# IcantFindFileName.net
KiCad netlist of a schematic drawn in Altium Designer
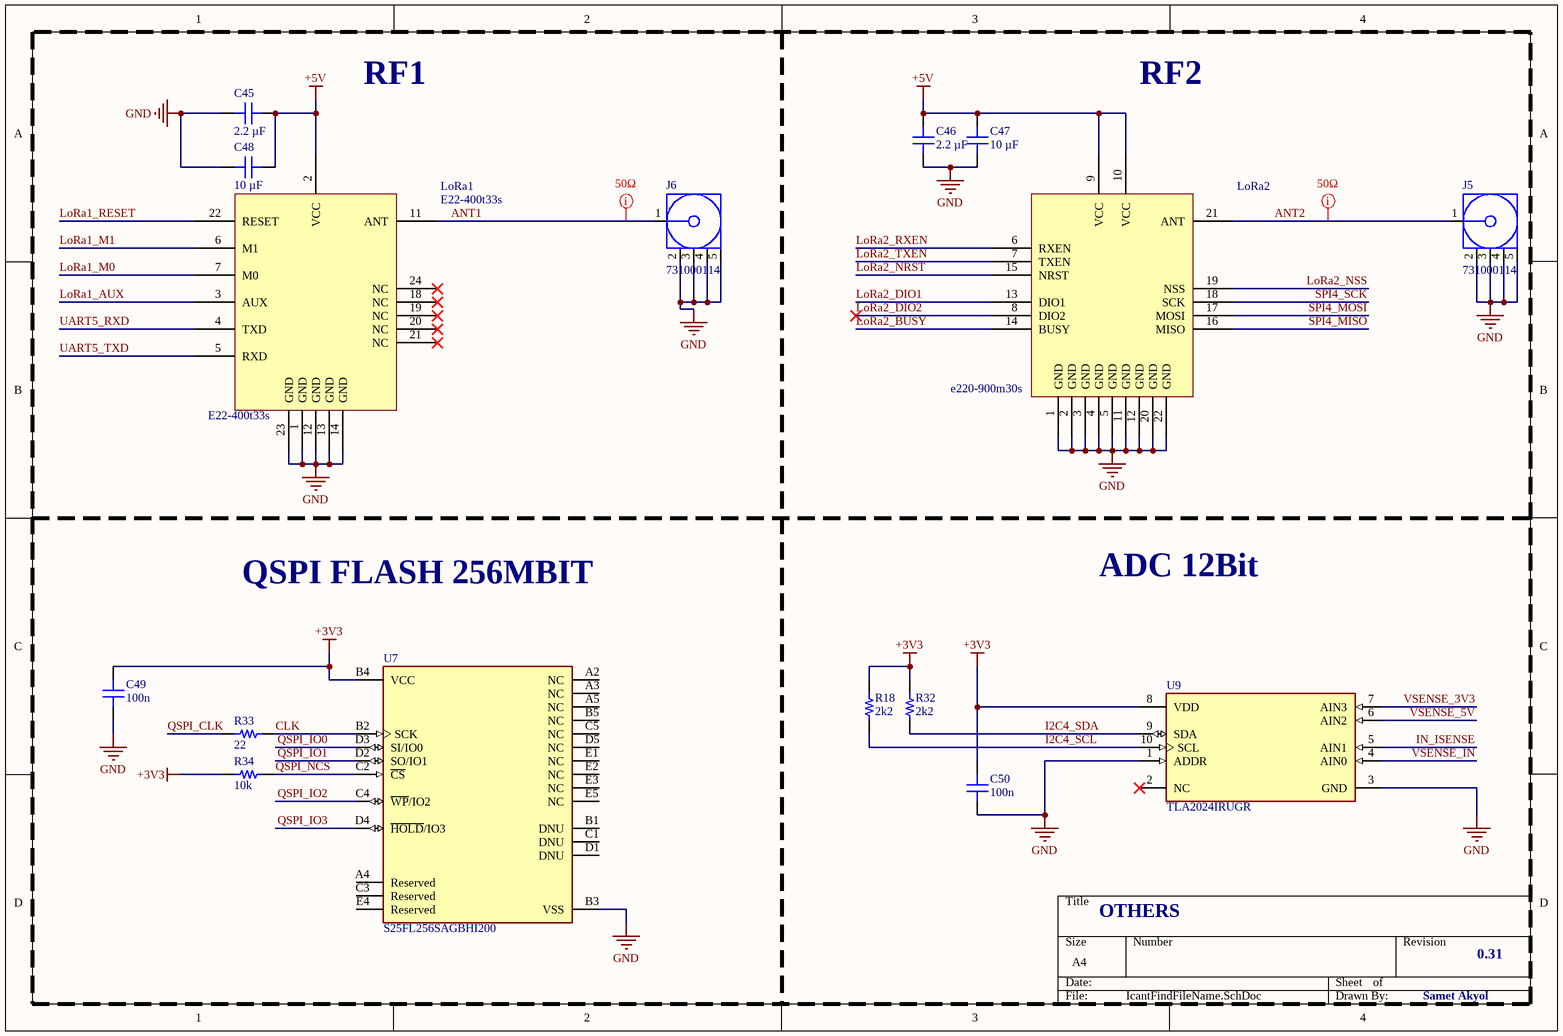
[diagram p0: IcantFindFileName.SchDoc]

(export (version "E")
  (design (tool "Eeschema 10.0.6"))
  (components
    (comp (ref "C45")
      (value "2.2 µF")
      (footprint "CAP 0805_2012")
      (description "CAP CER 2.2UF 25V X7R 0805")
      (fields (field (name "PART NUMBER") "TMK212B7225MG-TR") (field (name "MANUFACTURER") "Taiyo Yuden"))
      (libsource (lib "Celestial Altium Library - altium_library") (part "Capacitor"))
    )
    (comp (ref "C46")
      (value "2.2 µF")
      (footprint "CAP 0805_2012")
      (description "CAP CER 2.2UF 25V X7R 0805")
      (fields (field (name "PART NUMBER") "TMK212B7225MG-TR") (field (name "MANUFACTURER") "Taiyo Yuden"))
      (libsource (lib "Celestial Altium Library - altium_library") (part "Capacitor"))
    )
    (comp (ref "C47")
      (value "10 µF")
      (footprint "CAP 0805_2012")
      (description "CAP CER 10UF 16V X6S 0805")
      (fields
        (field (name "PART NUMBER") "C2012X6S1C106K125AC")
        (field (name "MANUFACTURER") "TDK Corporation")
      )
      (libsource (lib "Celestial Altium Library - altium_library") (part "Capacitor"))
    )
    (comp (ref "C48")
      (value "10 µF")
      (footprint "CAP 0805_2012")
      (description "CAP CER 10UF 16V X6S 0805")
      (fields
        (field (name "PART NUMBER") "C2012X6S1C106K125AC")
        (field (name "MANUFACTURER") "TDK Corporation")
      )
      (libsource (lib "Celestial Altium Library - altium_library") (part "Capacitor"))
    )
    (comp (ref "C49")
      (value "100n")
      (footprint "CAP 0402_1005")
      (description "CAP CER 100NF 10V X7R 0402")
      (fields
        (field (name "PART NUMBER") "CL05B104KP5VPNC")
        (field (name "MANUFACTURER") "Samsung Electro-Mechanics")
      )
      (libsource (lib "Celestial Altium Library - altium_library") (part "Capacitor"))
    )
    (comp (ref "C50")
      (value "100n")
      (footprint "CAP 0402_1005")
      (description "CAP CER 100NF 10V X7R 0402")
      (fields
        (field (name "PART NUMBER") "CL05B104KP5VPNC")
        (field (name "MANUFACTURER") "Samsung Electro-Mechanics")
      )
      (libsource (lib "Celestial Altium Library - altium_library") (part "Capacitor"))
    )
    (comp (ref "J5")
      (value "731000114")
      (footprint "MOLX-731000114_V")
      (description "SMA Right-Angle PCB Jack Receptacle, Brass Body, Gold Plated, 50 Ohm, 5-Pin THD, RoHS, Tray")
      (fields (field (name "MANUFACTURER") "Molex"))
      (libsource (lib "Altium Content Vault") (part "CN-S-4F-RF5"))
    )
    (comp (ref "J6")
      (value "731000114")
      (footprint "MOLX-731000114_V")
      (description "SMA Right-Angle PCB Jack Receptacle, Brass Body, Gold Plated, 50 Ohm, 5-Pin THD, RoHS, Tray")
      (fields (field (name "MANUFACTURER") "Molex"))
      (libsource (lib "Altium Content Vault") (part "CN-S-4F-RF5"))
    )
    (comp (ref "LoRa1")
      (value "E22-400t33s")
      (footprint "E32-433T33S")
      (libsource (lib "LoraE220-400t33s") (part "LoRa"))
    )
    (comp (ref "LoRa2")
      (value "e220-900m30s")
      (footprint "PE220-900M30S")
      (libsource (lib "LoRaE220-900m30s") (part "LoRaE220-900m30s"))
    )
    (comp (ref "R18")
      (value "2k2")
      (footprint "RES 0402_1005")
      (description "RES 10K OHM 0.1% 1/10W 0402")
      (fields
        (field (name "PART NUMBER") "RP73PF1E10KBTD")
        (field (name "MANUFACTURER") "TE Connectivity Passive Product")
      )
      (libsource (lib "Celestial Altium Library - altium_library") (part "Resistor"))
    )
    (comp (ref "R32")
      (value "2k2")
      (footprint "RES 0402_1005")
      (description "RES 10K OHM 0.1% 1/10W 0402")
      (fields
        (field (name "PART NUMBER") "RP73PF1E10KBTD")
        (field (name "MANUFACTURER") "TE Connectivity Passive Product")
      )
      (libsource (lib "Celestial Altium Library - altium_library") (part "Resistor"))
    )
    (comp (ref "R33")
      (value "22")
      (footprint "RES 0402_1005")
      (description "RES SMD 22 OHM 0.5% 1/16W 0402")
      (fields
        (field (name "PART NUMBER") "ERA-2AKD220X")
        (field (name "MANUFACTURER") "Panasonic Electronic Components")
      )
      (libsource (lib "Celestial Altium Library - altium_library") (part "Resistor"))
    )
    (comp (ref "R34")
      (value "10k")
      (footprint "RES 0402_1005")
      (description "RES 10K OHM 0.1% 1/10W 0402")
      (fields
        (field (name "PART NUMBER") "RP73PF1E10KBTD")
        (field (name "MANUFACTURER") "TE Connectivity Passive Product")
      )
      (libsource (lib "Celestial Altium Library - altium_library") (part "Resistor"))
    )
    (comp (ref "U7")
      (value "S25FL256SAGBHI200")
      (footprint "FP-002-15534-MFG")
      (description "IC FLASH 256M SPI 133MHZ 24BGA")
      (fields
        (field (name "MANUFACTURER") "Cypress Semiconductor")
        (field (name "OCTOPART") "https://octopart.com/s25fl256sagbhi200-cypress+semiconductor-65153244")
      )
      (libsource (lib "Altium Content Vault") (part "c77b842a4ee4074ef0a45385ad30001"))
    )
    (comp (ref "U9")
      (value "TLA2024IRUGR")
      (footprint "FP-RUG0010A-MFG")
      (description "IC ADC 12BIT SIGMA-DELTA 10X2QFN")
      (libsource (lib "Altium Content Vault") (part "eb3f1feaf096e0a4fed058628c4118d"))
    )
  )
  (nets
    (net (code "1") (name "+3V3") (class "Default")
      (node (ref "C49") (pin "2") (pinfunction "2_2") (pintype "passive"))
      (node (ref "C50") (pin "2") (pinfunction "2_2") (pintype "passive"))
      (node (ref "R18") (pin "2") (pinfunction "2_2") (pintype "passive"))
      (node (ref "R32") (pin "2") (pinfunction "2_2") (pintype "passive"))
      (node (ref "R34") (pin "2") (pinfunction "2_2") (pintype "passive"))
      (node (ref "U7") (pin "B4") (pinfunction "VCC_B4") (pintype "power_in"))
      (node (ref "U9") (pin "8") (pinfunction "VDD_8") (pintype "power_in"))
    )
    (net (code "2") (name "+5V") (class "Default")
      (node (ref "C45") (pin "2") (pinfunction "2_2") (pintype "passive"))
      (node (ref "C46") (pin "2") (pinfunction "2_2") (pintype "passive"))
      (node (ref "C47") (pin "2") (pinfunction "2_2") (pintype "passive"))
      (node (ref "C48") (pin "2") (pinfunction "2_2") (pintype "passive"))
      (node (ref "LoRa1") (pin "2") (pinfunction "VCC_2") (pintype "passive"))
      (node (ref "LoRa2") (pin "10") (pinfunction "VCC_10") (pintype "passive"))
      (node (ref "LoRa2") (pin "9") (pinfunction "VCC_9") (pintype "passive"))
    )
    (net (code "3") (name "/ANT1") (class "Default")
      (node (ref "J6") (pin "1") (pinfunction "1_1") (pintype "passive"))
      (node (ref "LoRa1") (pin "11") (pinfunction "ANT_11") (pintype "passive"))
    )
    (net (code "4") (name "/ANT2") (class "Default")
      (node (ref "J5") (pin "1") (pinfunction "1_1") (pintype "passive"))
      (node (ref "LoRa2") (pin "21") (pinfunction "ANT_21") (pintype "passive"))
    )
    (net (code "5") (name "/CLK") (class "Default")
      (node (ref "R33") (pin "2") (pinfunction "2_2") (pintype "passive"))
      (node (ref "U7") (pin "B2") (pinfunction "SCK_B2") (pintype "input"))
    )
    (net (code "6") (name "/I2C4_SCL") (class "Default")
      (node (ref "R18") (pin "1") (pinfunction "1_1") (pintype "passive"))
      (node (ref "U9") (pin "10") (pinfunction "SCL_10") (pintype "input"))
    )
    (net (code "7") (name "/I2C4_SDA") (class "Default")
      (node (ref "R32") (pin "1") (pinfunction "1_1") (pintype "passive"))
      (node (ref "U9") (pin "9") (pinfunction "SDA_9") (pintype "bidirectional"))
    )
    (net (code "8") (name "/IN_ISENSE") (class "Default")
      (node (ref "U9") (pin "5") (pinfunction "AIN1_5") (pintype "input"))
    )
    (net (code "9") (name "/LoRa1_AUX") (class "Default")
      (node (ref "LoRa1") (pin "3") (pinfunction "AUX_3") (pintype "passive"))
    )
    (net (code "10") (name "/LoRa1_M0") (class "Default")
      (node (ref "LoRa1") (pin "7") (pinfunction "M0_7") (pintype "passive"))
    )
    (net (code "11") (name "/LoRa1_M1") (class "Default")
      (node (ref "LoRa1") (pin "6") (pinfunction "M1_6") (pintype "passive"))
    )
    (net (code "12") (name "/LoRa1_RESET") (class "Default")
      (node (ref "LoRa1") (pin "22") (pinfunction "RESET_22") (pintype "passive"))
    )
    (net (code "13") (name "/LoRa2_BUSY") (class "Default")
      (node (ref "LoRa2") (pin "14") (pinfunction "BUSY_14") (pintype "passive"))
    )
    (net (code "14") (name "/LoRa2_DIO1") (class "Default")
      (node (ref "LoRa2") (pin "13") (pinfunction "DIO1_13") (pintype "passive"))
    )
    (net (code "15") (name "/LoRa2_DIO2") (class "Default")
      (node (ref "LoRa2") (pin "8") (pinfunction "DIO2_8") (pintype "passive+no_connect"))
    )
    (net (code "16") (name "/LoRa2_NRST") (class "Default")
      (node (ref "LoRa2") (pin "15") (pinfunction "NRST_15") (pintype "passive"))
    )
    (net (code "17") (name "/LoRa2_NSS") (class "Default")
      (node (ref "LoRa2") (pin "19") (pinfunction "NSS_19") (pintype "passive"))
    )
    (net (code "18") (name "/LoRa2_RXEN") (class "Default")
      (node (ref "LoRa2") (pin "6") (pinfunction "RXEN_6") (pintype "passive"))
    )
    (net (code "19") (name "/LoRa2_TXEN") (class "Default")
      (node (ref "LoRa2") (pin "7") (pinfunction "TXEN_7") (pintype "passive"))
    )
    (net (code "20") (name "/QSPI_CLK") (class "Default")
      (node (ref "R33") (pin "1") (pinfunction "1_1") (pintype "passive"))
    )
    (net (code "21") (name "/QSPI_IO0") (class "Default")
      (node (ref "U7") (pin "D3") (pinfunction "SI/IO0_D3") (pintype "bidirectional"))
    )
    (net (code "22") (name "/QSPI_IO1") (class "Default")
      (node (ref "U7") (pin "D2") (pinfunction "SO/IO1_D2") (pintype "bidirectional"))
    )
    (net (code "23") (name "/QSPI_IO2") (class "Default")
      (node (ref "U7") (pin "C4") (pinfunction "~{WP}/IO2_C4") (pintype "bidirectional"))
    )
    (net (code "24") (name "/QSPI_IO3") (class "Default")
      (node (ref "U7") (pin "D4") (pinfunction "~{HOLD}/IO3_D4") (pintype "bidirectional"))
    )
    (net (code "25") (name "/QSPI_NCS") (class "Default")
      (node (ref "R34") (pin "1") (pinfunction "1_1") (pintype "passive"))
      (node (ref "U7") (pin "C2") (pinfunction "~{CS}_C2") (pintype "input"))
    )
    (net (code "26") (name "/SPI4_MISO") (class "Default")
      (node (ref "LoRa2") (pin "16") (pinfunction "MISO_16") (pintype "passive"))
    )
    (net (code "27") (name "/SPI4_MOSI") (class "Default")
      (node (ref "LoRa2") (pin "17") (pinfunction "MOSI_17") (pintype "passive"))
    )
    (net (code "28") (name "/SPI4_SCK") (class "Default")
      (node (ref "LoRa2") (pin "18") (pinfunction "SCK_18") (pintype "passive"))
    )
    (net (code "29") (name "/UART5_RXD") (class "Default")
      (node (ref "LoRa1") (pin "4") (pinfunction "TXD_4") (pintype "passive"))
    )
    (net (code "30") (name "/UART5_TXD") (class "Default")
      (node (ref "LoRa1") (pin "5") (pinfunction "RXD_5") (pintype "passive"))
    )
    (net (code "31") (name "/VSENSE_3V3") (class "Default")
      (node (ref "U9") (pin "7") (pinfunction "AIN3_7") (pintype "input"))
    )
    (net (code "32") (name "/VSENSE_5V") (class "Default")
      (node (ref "U9") (pin "6") (pinfunction "AIN2_6") (pintype "input"))
    )
    (net (code "33") (name "/VSENSE_IN") (class "Default")
      (node (ref "U9") (pin "4") (pinfunction "AIN0_4") (pintype "input"))
    )
    (net (code "34") (name "GND") (class "Default")
      (node (ref "C45") (pin "1") (pinfunction "1_1") (pintype "passive"))
      (node (ref "C46") (pin "1") (pinfunction "1_1") (pintype "passive"))
      (node (ref "C47") (pin "1") (pinfunction "1_1") (pintype "passive"))
      (node (ref "C48") (pin "1") (pinfunction "1_1") (pintype "passive"))
      (node (ref "C49") (pin "1") (pinfunction "1_1") (pintype "passive"))
      (node (ref "C50") (pin "1") (pinfunction "1_1") (pintype "passive"))
      (node (ref "J5") (pin "2") (pinfunction "2_2") (pintype "passive"))
      (node (ref "J5") (pin "3") (pinfunction "3_3") (pintype "passive"))
      (node (ref "J5") (pin "4") (pinfunction "4_4") (pintype "passive"))
      (node (ref "J5") (pin "5") (pinfunction "5_5") (pintype "passive"))
      (node (ref "J6") (pin "2") (pinfunction "2_2") (pintype "passive"))
      (node (ref "J6") (pin "3") (pinfunction "3_3") (pintype "passive"))
      (node (ref "J6") (pin "4") (pinfunction "4_4") (pintype "passive"))
      (node (ref "J6") (pin "5") (pinfunction "5_5") (pintype "passive"))
      (node (ref "LoRa1") (pin "1") (pinfunction "GND_1") (pintype "passive"))
      (node (ref "LoRa1") (pin "12") (pinfunction "GND_12") (pintype "passive"))
      (node (ref "LoRa1") (pin "13") (pinfunction "GND_13") (pintype "passive"))
      (node (ref "LoRa1") (pin "14") (pinfunction "GND_14") (pintype "passive"))
      (node (ref "LoRa1") (pin "23") (pinfunction "GND_23") (pintype "passive"))
      (node (ref "LoRa2") (pin "1") (pinfunction "GND_1") (pintype "passive"))
      (node (ref "LoRa2") (pin "11") (pinfunction "GND_11") (pintype "passive"))
      (node (ref "LoRa2") (pin "12") (pinfunction "GND_12") (pintype "passive"))
      (node (ref "LoRa2") (pin "2") (pinfunction "GND_2") (pintype "passive"))
      (node (ref "LoRa2") (pin "20") (pinfunction "GND_20") (pintype "passive"))
      (node (ref "LoRa2") (pin "22") (pinfunction "GND_22") (pintype "passive"))
      (node (ref "LoRa2") (pin "3") (pinfunction "GND_3") (pintype "passive"))
      (node (ref "LoRa2") (pin "4") (pinfunction "GND_4") (pintype "passive"))
      (node (ref "LoRa2") (pin "5") (pinfunction "GND_5") (pintype "passive"))
      (node (ref "U7") (pin "B3") (pinfunction "VSS_B3") (pintype "power_in"))
      (node (ref "U9") (pin "1") (pinfunction "ADDR_1") (pintype "input"))
      (node (ref "U9") (pin "3") (pinfunction "GND_3") (pintype "power_in"))
    )
    (net (code "35") (name "unconnected-(LoRa1-NC-Pad18)") (class "Default")
      (node (ref "LoRa1") (pin "18") (pinfunction "NC_18") (pintype "passive+no_connect"))
    )
    (net (code "36") (name "unconnected-(LoRa1-NC-Pad19)") (class "Default")
      (node (ref "LoRa1") (pin "19") (pinfunction "NC_19") (pintype "passive+no_connect"))
    )
    (net (code "37") (name "unconnected-(LoRa1-NC-Pad20)") (class "Default")
      (node (ref "LoRa1") (pin "20") (pinfunction "NC_20") (pintype "passive+no_connect"))
    )
    (net (code "38") (name "unconnected-(LoRa1-NC-Pad21)") (class "Default")
      (node (ref "LoRa1") (pin "21") (pinfunction "NC_21") (pintype "passive+no_connect"))
    )
    (net (code "39") (name "unconnected-(LoRa1-NC-Pad24)") (class "Default")
      (node (ref "LoRa1") (pin "24") (pinfunction "NC_24") (pintype "passive+no_connect"))
    )
    (net (code "40") (name "unconnected-(U7-DNU-PadB1)") (class "Default")
      (node (ref "U7") (pin "B1") (pinfunction "DNU_B1") (pintype "passive"))
    )
    (net (code "41") (name "unconnected-(U7-DNU-PadC1)") (class "Default")
      (node (ref "U7") (pin "C1") (pinfunction "DNU_C1") (pintype "passive"))
    )
    (net (code "42") (name "unconnected-(U7-DNU-PadD1)") (class "Default")
      (node (ref "U7") (pin "D1") (pinfunction "DNU_D1") (pintype "passive"))
    )
    (net (code "43") (name "unconnected-(U7-NC-PadA2)") (class "Default")
      (node (ref "U7") (pin "A2") (pinfunction "NC_A2") (pintype "passive"))
    )
    (net (code "44") (name "unconnected-(U7-NC-PadA3)") (class "Default")
      (node (ref "U7") (pin "A3") (pinfunction "NC_A3") (pintype "passive"))
    )
    (net (code "45") (name "unconnected-(U7-NC-PadA5)") (class "Default")
      (node (ref "U7") (pin "A5") (pinfunction "NC_A5") (pintype "passive"))
    )
    (net (code "46") (name "unconnected-(U7-NC-PadB5)") (class "Default")
      (node (ref "U7") (pin "B5") (pinfunction "NC_B5") (pintype "passive"))
    )
    (net (code "47") (name "unconnected-(U7-NC-PadC5)") (class "Default")
      (node (ref "U7") (pin "C5") (pinfunction "NC_C5") (pintype "passive"))
    )
    (net (code "48") (name "unconnected-(U7-NC-PadD5)") (class "Default")
      (node (ref "U7") (pin "D5") (pinfunction "NC_D5") (pintype "passive"))
    )
    (net (code "49") (name "unconnected-(U7-NC-PadE1)") (class "Default")
      (node (ref "U7") (pin "E1") (pinfunction "NC_E1") (pintype "passive"))
    )
    (net (code "50") (name "unconnected-(U7-NC-PadE2)") (class "Default")
      (node (ref "U7") (pin "E2") (pinfunction "NC_E2") (pintype "passive"))
    )
    (net (code "51") (name "unconnected-(U7-NC-PadE3)") (class "Default")
      (node (ref "U7") (pin "E3") (pinfunction "NC_E3") (pintype "passive"))
    )
    (net (code "52") (name "unconnected-(U7-NC-PadE5)") (class "Default")
      (node (ref "U7") (pin "E5") (pinfunction "NC_E5") (pintype "passive"))
    )
    (net (code "53") (name "unconnected-(U7-Reserved-PadA4)") (class "Default")
      (node (ref "U7") (pin "A4") (pinfunction "Reserved_A4") (pintype "passive"))
    )
    (net (code "54") (name "unconnected-(U7-Reserved-PadC3)") (class "Default")
      (node (ref "U7") (pin "C3") (pinfunction "Reserved_C3") (pintype "passive"))
    )
    (net (code "55") (name "unconnected-(U7-Reserved-PadE4)") (class "Default")
      (node (ref "U7") (pin "E4") (pinfunction "Reserved_E4") (pintype "passive"))
    )
    (net (code "56") (name "unconnected-(U9-NC-Pad2)") (class "Default")
      (node (ref "U9") (pin "2") (pinfunction "NC_2") (pintype "passive+no_connect"))
    )
  )
)
